# NNP-DWG-125-001-000_PG4_Schematic_Drawin.net
KiCad netlist of a schematic drawn in Altium Designer
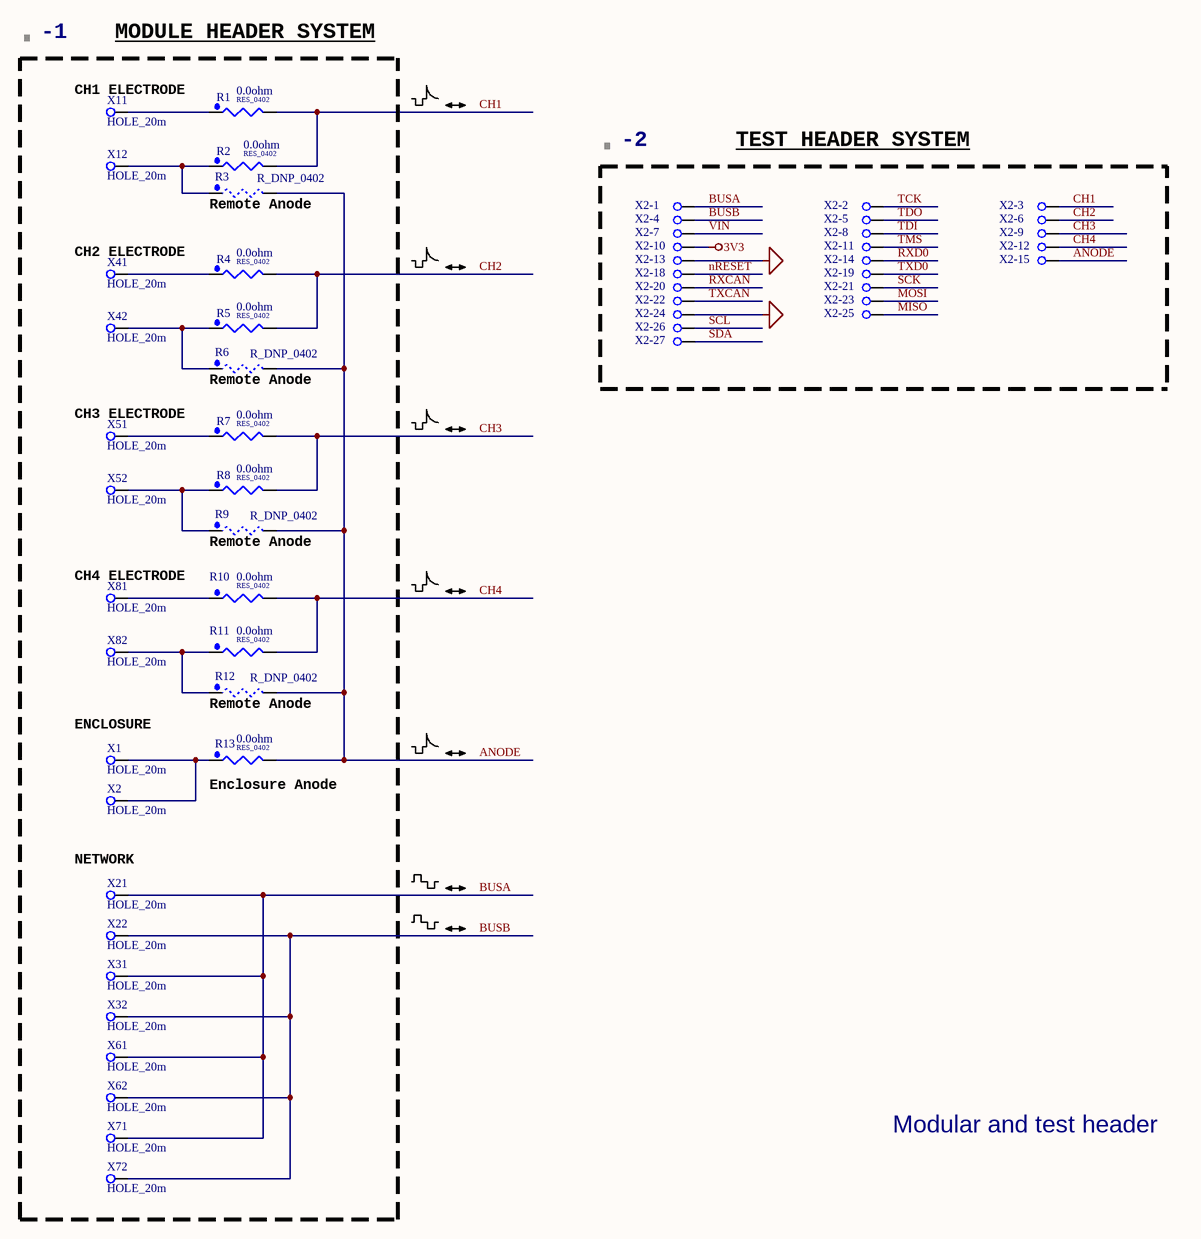
[diagram p0: NNP-DWG-125-001-000 PG4 Schematic Drawing Pg4.SchDoc]

(export (version "E")
  (design (tool "Eeschema 10.0.6"))
  (components
    (comp (ref "-1")
      (value "BOM_S1")
      (description "BOM item small graphic")
      (fields (field (name "XDESCRIPTION") "MODULE HEADER SYSTEM"))
      (libsource (lib "BOM_sym") (part "BOM_S1"))
    )
    (comp (ref "-2")
      (value "BOM_S1")
      (description "BOM item small graphic")
      (fields (field (name "XDESCRIPTION") "TEST HEADER SYSTEM"))
      (libsource (lib "BOM_sym") (part "BOM_S1"))
    )
    (comp (ref "R1")
      (value "0.0ohm")
      (footprint "RES_0402")
      (description "0.0 ohm, 1/16W, 0402, RoHS")
      (fields
        (field (name "MFR") "Vishay Dale")
        (field (name "PACKAGEDESCRIPTION") "RES_0402")
        (field (name "MPN") "CRCW04020000Z0ED")
      )
      (libsource (lib "NNPS Integrated Parts") (part "MCR01MZPJ000"))
    )
    (comp (ref "R2")
      (value "0.0ohm")
      (footprint "RES_0402")
      (description "0.0 ohm, 1/16W, 0402, RoHS")
      (fields
        (field (name "MFR") "Vishay Dale")
        (field (name "PACKAGEDESCRIPTION") "RES_0402")
        (field (name "MPN") "CRCW04020000Z0ED")
      )
      (libsource (lib "NNPS Integrated Parts") (part "MCR01MZPJ000"))
    )
    (comp (ref "R3")
      (value "R_DNP_0402")
      (footprint "RES_0402")
      (description "0.0 ohm 1/16W smd 0402 RoHS")
      (fields (field (name "MFR") "DO NOT POPULATE"))
      (libsource (lib "NNPS Integrated Parts") (part "R_DNP_0402"))
    )
    (comp (ref "R4")
      (value "0.0ohm")
      (footprint "RES_0402")
      (description "0.0 ohm, 1/16W, 0402, RoHS")
      (fields
        (field (name "MFR") "Vishay Dale")
        (field (name "PACKAGEDESCRIPTION") "RES_0402")
        (field (name "MPN") "CRCW04020000Z0ED")
      )
      (libsource (lib "NNPS Integrated Parts") (part "MCR01MZPJ000"))
    )
    (comp (ref "R5")
      (value "0.0ohm")
      (footprint "RES_0402")
      (description "0.0 ohm, 1/16W, 0402, RoHS")
      (fields
        (field (name "MFR") "Vishay Dale")
        (field (name "PACKAGEDESCRIPTION") "RES_0402")
        (field (name "MPN") "CRCW04020000Z0ED")
      )
      (libsource (lib "NNPS Integrated Parts") (part "MCR01MZPJ000"))
    )
    (comp (ref "R6")
      (value "R_DNP_0402")
      (footprint "RES_0402")
      (description "0.0 ohm 1/16W smd 0402 RoHS")
      (fields (field (name "MFR") "DO NOT POPULATE"))
      (libsource (lib "NNPS Integrated Parts") (part "R_DNP_0402"))
    )
    (comp (ref "R7")
      (value "0.0ohm")
      (footprint "RES_0402")
      (description "0.0 ohm, 1/16W, 0402, RoHS")
      (fields
        (field (name "MFR") "Vishay Dale")
        (field (name "PACKAGEDESCRIPTION") "RES_0402")
        (field (name "MPN") "CRCW04020000Z0ED")
      )
      (libsource (lib "NNPS Integrated Parts") (part "MCR01MZPJ000"))
    )
    (comp (ref "R8")
      (value "0.0ohm")
      (footprint "RES_0402")
      (description "0.0 ohm, 1/16W, 0402, RoHS")
      (fields
        (field (name "MFR") "Vishay Dale")
        (field (name "PACKAGEDESCRIPTION") "RES_0402")
        (field (name "MPN") "CRCW04020000Z0ED")
      )
      (libsource (lib "NNPS Integrated Parts") (part "MCR01MZPJ000"))
    )
    (comp (ref "R9")
      (value "R_DNP_0402")
      (footprint "RES_0402")
      (description "0.0 ohm 1/16W smd 0402 RoHS")
      (fields (field (name "MFR") "DO NOT POPULATE"))
      (libsource (lib "NNPS Integrated Parts") (part "R_DNP_0402"))
    )
    (comp (ref "R10")
      (value "0.0ohm")
      (footprint "RES_0402")
      (description "0.0 ohm, 1/16W, 0402, RoHS")
      (fields
        (field (name "MFR") "Vishay Dale")
        (field (name "PACKAGEDESCRIPTION") "RES_0402")
        (field (name "MPN") "CRCW04020000Z0ED")
      )
      (libsource (lib "NNPS Integrated Parts") (part "MCR01MZPJ000"))
    )
    (comp (ref "R11")
      (value "0.0ohm")
      (footprint "RES_0402")
      (description "0.0 ohm, 1/16W, 0402, RoHS")
      (fields
        (field (name "MFR") "Vishay Dale")
        (field (name "PACKAGEDESCRIPTION") "RES_0402")
        (field (name "MPN") "CRCW04020000Z0ED")
      )
      (libsource (lib "NNPS Integrated Parts") (part "MCR01MZPJ000"))
    )
    (comp (ref "R12")
      (value "R_DNP_0402")
      (footprint "RES_0402")
      (description "0.0 ohm 1/16W smd 0402 RoHS")
      (fields (field (name "MFR") "DO NOT POPULATE"))
      (libsource (lib "NNPS Integrated Parts") (part "R_DNP_0402"))
    )
    (comp (ref "R13")
      (value "0.0ohm")
      (footprint "RES_0402")
      (description "0.0 ohm, 1/16W, 0402, RoHS")
      (fields
        (field (name "MFR") "Vishay Dale")
        (field (name "PACKAGEDESCRIPTION") "RES_0402")
        (field (name "MPN") "CRCW04020000Z0ED")
      )
      (libsource (lib "NNPS Integrated Parts") (part "MCR01MZPJ000"))
    )
    (comp (ref "X1")
      (value "HOLE_20m")
      (footprint "FEEDHOLE_20mil")
      (description "Hole for 10mil diameter feedthrough")
      (libsource (lib "NNPS Integrated Parts") (part "HOLE_20m"))
    )
    (comp (ref "X2")
      (value "HOLE_20m")
      (footprint "FEEDHOLE_20mil")
      (description "Hole for 10mil diameter feedthrough")
      (libsource (lib "NNPS Integrated Parts") (part "HOLE_20m"))
    )
    (comp (ref "X2-1")
      (value "0.1\" header hole")
      (footprint "HDR_HOLE_RING")
      (libsource (lib "NNPS Integrated Parts") (part "Header 1x1"))
    )
    (comp (ref "X2-2")
      (value "0.1\" header hole")
      (footprint "HDR_HOLE_RING")
      (libsource (lib "NNPS Integrated Parts") (part "Header 1x1"))
    )
    (comp (ref "X2-3")
      (value "0.1\" header hole")
      (footprint "HDR_HOLE_RING")
      (libsource (lib "NNPS Integrated Parts") (part "Header 1x1"))
    )
    (comp (ref "X2-4")
      (value "0.1\" header hole")
      (footprint "HDR_HOLE_RING")
      (libsource (lib "NNPS Integrated Parts") (part "Header 1x1"))
    )
    (comp (ref "X2-5")
      (value "0.1\" header hole")
      (footprint "HDR_HOLE_RING")
      (libsource (lib "NNPS Integrated Parts") (part "Header 1x1"))
    )
    (comp (ref "X2-6")
      (value "0.1\" header hole")
      (footprint "HDR_HOLE_RING")
      (libsource (lib "NNPS Integrated Parts") (part "Header 1x1"))
    )
    (comp (ref "X2-7")
      (value "0.1\" header hole")
      (footprint "HDR_HOLE_RING")
      (libsource (lib "NNPS Integrated Parts") (part "Header 1x1"))
    )
    (comp (ref "X2-8")
      (value "0.1\" header hole")
      (footprint "HDR_HOLE_RING")
      (libsource (lib "NNPS Integrated Parts") (part "Header 1x1"))
    )
    (comp (ref "X2-9")
      (value "0.1\" header hole")
      (footprint "HDR_HOLE_RING")
      (libsource (lib "NNPS Integrated Parts") (part "Header 1x1"))
    )
    (comp (ref "X2-10")
      (value "0.1\" header hole")
      (footprint "HDR_HOLE_RING")
      (libsource (lib "NNPS Integrated Parts") (part "Header 1x1"))
    )
    (comp (ref "X2-11")
      (value "0.1\" header hole")
      (footprint "HDR_HOLE_RING")
      (libsource (lib "NNPS Integrated Parts") (part "Header 1x1"))
    )
    (comp (ref "X2-12")
      (value "0.1\" header hole")
      (footprint "HDR_HOLE_RING")
      (libsource (lib "NNPS Integrated Parts") (part "Header 1x1"))
    )
    (comp (ref "X2-13")
      (value "0.1\" header hole")
      (footprint "HDR_HOLE_RING")
      (libsource (lib "NNPS Integrated Parts") (part "Header 1x1"))
    )
    (comp (ref "X2-14")
      (value "0.1\" header hole")
      (footprint "HDR_HOLE_RING")
      (libsource (lib "NNPS Integrated Parts") (part "Header 1x1"))
    )
    (comp (ref "X2-15")
      (value "0.1\" header hole")
      (footprint "HDR_HOLE_RING")
      (libsource (lib "NNPS Integrated Parts") (part "Header 1x1"))
    )
    (comp (ref "X2-18")
      (value "0.1\" header hole")
      (footprint "HDR_HOLE_RING")
      (libsource (lib "NNPS Integrated Parts") (part "Header 1x1"))
    )
    (comp (ref "X2-19")
      (value "0.1\" header hole")
      (footprint "HDR_HOLE_RING")
      (libsource (lib "NNPS Integrated Parts") (part "Header 1x1"))
    )
    (comp (ref "X2-20")
      (value "0.1\" header hole")
      (footprint "HDR_HOLE_RING")
      (libsource (lib "NNPS Integrated Parts") (part "Header 1x1"))
    )
    (comp (ref "X2-21")
      (value "0.1\" header hole")
      (footprint "HDR_HOLE_RING")
      (libsource (lib "NNPS Integrated Parts") (part "Header 1x1"))
    )
    (comp (ref "X2-22")
      (value "0.1\" header hole")
      (footprint "HDR_HOLE_RING")
      (libsource (lib "NNPS Integrated Parts") (part "Header 1x1"))
    )
    (comp (ref "X2-23")
      (value "0.1\" header hole")
      (footprint "HDR_HOLE_RING")
      (libsource (lib "NNPS Integrated Parts") (part "Header 1x1"))
    )
    (comp (ref "X2-24")
      (value "0.1\" header hole")
      (footprint "HDR_HOLE_RING")
      (libsource (lib "NNPS Integrated Parts") (part "Header 1x1"))
    )
    (comp (ref "X2-25")
      (value "0.1\" header hole")
      (footprint "HDR_HOLE_RING")
      (libsource (lib "NNPS Integrated Parts") (part "Header 1x1"))
    )
    (comp (ref "X2-26")
      (value "0.1\" header hole")
      (footprint "HDR_HOLE_RING")
      (libsource (lib "NNPS Integrated Parts") (part "Header 1x1"))
    )
    (comp (ref "X2-27")
      (value "0.1\" header hole")
      (footprint "HDR_HOLE_RING")
      (libsource (lib "NNPS Integrated Parts") (part "Header 1x1"))
    )
    (comp (ref "X11")
      (value "HOLE_20m")
      (footprint "FEEDHOLE_20mil")
      (description "Hole for 10mil diameter feedthrough")
      (libsource (lib "NNPS Integrated Parts") (part "HOLE_20m"))
    )
    (comp (ref "X12")
      (value "HOLE_20m")
      (footprint "FEEDHOLE_20mil")
      (description "Hole for 10mil diameter feedthrough")
      (libsource (lib "NNPS Integrated Parts") (part "HOLE_20m"))
    )
    (comp (ref "X21")
      (value "HOLE_20m")
      (footprint "FEEDHOLE_20mil")
      (description "Hole for 10mil diameter feedthrough")
      (libsource (lib "NNPS Integrated Parts") (part "HOLE_20m"))
    )
    (comp (ref "X22")
      (value "HOLE_20m")
      (footprint "FEEDHOLE_20mil")
      (description "Hole for 10mil diameter feedthrough")
      (libsource (lib "NNPS Integrated Parts") (part "HOLE_20m"))
    )
    (comp (ref "X31")
      (value "HOLE_20m")
      (footprint "FEEDHOLE_20mil")
      (description "Hole for 10mil diameter feedthrough")
      (libsource (lib "NNPS Integrated Parts") (part "HOLE_20m"))
    )
    (comp (ref "X32")
      (value "HOLE_20m")
      (footprint "FEEDHOLE_20mil")
      (description "Hole for 10mil diameter feedthrough")
      (libsource (lib "NNPS Integrated Parts") (part "HOLE_20m"))
    )
    (comp (ref "X41")
      (value "HOLE_20m")
      (footprint "FEEDHOLE_20mil")
      (description "Hole for 10mil diameter feedthrough")
      (libsource (lib "NNPS Integrated Parts") (part "HOLE_20m"))
    )
    (comp (ref "X42")
      (value "HOLE_20m")
      (footprint "FEEDHOLE_20mil")
      (description "Hole for 10mil diameter feedthrough")
      (libsource (lib "NNPS Integrated Parts") (part "HOLE_20m"))
    )
    (comp (ref "X51")
      (value "HOLE_20m")
      (footprint "FEEDHOLE_20mil")
      (description "Hole for 10mil diameter feedthrough")
      (libsource (lib "NNPS Integrated Parts") (part "HOLE_20m"))
    )
    (comp (ref "X52")
      (value "HOLE_20m")
      (footprint "FEEDHOLE_20mil")
      (description "Hole for 10mil diameter feedthrough")
      (libsource (lib "NNPS Integrated Parts") (part "HOLE_20m"))
    )
    (comp (ref "X61")
      (value "HOLE_20m")
      (footprint "FEEDHOLE_20mil")
      (description "Hole for 10mil diameter feedthrough")
      (libsource (lib "NNPS Integrated Parts") (part "HOLE_20m"))
    )
    (comp (ref "X62")
      (value "HOLE_20m")
      (footprint "FEEDHOLE_20mil")
      (description "Hole for 10mil diameter feedthrough")
      (libsource (lib "NNPS Integrated Parts") (part "HOLE_20m"))
    )
    (comp (ref "X71")
      (value "HOLE_20m")
      (footprint "FEEDHOLE_20mil")
      (description "Hole for 10mil diameter feedthrough")
      (libsource (lib "NNPS Integrated Parts") (part "HOLE_20m"))
    )
    (comp (ref "X72")
      (value "HOLE_20m")
      (footprint "FEEDHOLE_20mil")
      (description "Hole for 10mil diameter feedthrough")
      (libsource (lib "NNPS Integrated Parts") (part "HOLE_20m"))
    )
    (comp (ref "X81")
      (value "HOLE_20m")
      (footprint "FEEDHOLE_20mil")
      (description "Hole for 10mil diameter feedthrough")
      (libsource (lib "NNPS Integrated Parts") (part "HOLE_20m"))
    )
    (comp (ref "X82")
      (value "HOLE_20m")
      (footprint "FEEDHOLE_20mil")
      (description "Hole for 10mil diameter feedthrough")
      (libsource (lib "NNPS Integrated Parts") (part "HOLE_20m"))
    )
  )
  (nets
    (net (code "1") (name "/ANODE") (class "Default")
      (node (ref "R12") (pin "2") (pinfunction "2_2") (pintype "passive"))
      (node (ref "R13") (pin "2") (pinfunction "2_2") (pintype "passive"))
      (node (ref "R3") (pin "2") (pinfunction "2_2") (pintype "passive"))
      (node (ref "R6") (pin "2") (pinfunction "2_2") (pintype "passive"))
      (node (ref "R9") (pin "2") (pinfunction "2_2") (pintype "passive"))
      (node (ref "X2-15") (pin "1") (pinfunction "1_1") (pintype "passive"))
    )
    (net (code "2") (name "/BUSA") (class "Default")
      (node (ref "X2-1") (pin "1") (pinfunction "1_1") (pintype "passive"))
      (node (ref "X21") (pin "1") (pinfunction "1_1") (pintype "passive"))
      (node (ref "X31") (pin "1") (pinfunction "1_1") (pintype "passive"))
      (node (ref "X61") (pin "1") (pinfunction "1_1") (pintype "passive"))
      (node (ref "X71") (pin "1") (pinfunction "1_1") (pintype "passive"))
    )
    (net (code "3") (name "/BUSB") (class "Default")
      (node (ref "X2-4") (pin "1") (pinfunction "1_1") (pintype "passive"))
      (node (ref "X22") (pin "1") (pinfunction "1_1") (pintype "passive"))
      (node (ref "X32") (pin "1") (pinfunction "1_1") (pintype "passive"))
      (node (ref "X62") (pin "1") (pinfunction "1_1") (pintype "passive"))
      (node (ref "X72") (pin "1") (pinfunction "1_1") (pintype "passive"))
    )
    (net (code "4") (name "/CH1") (class "Default")
      (node (ref "R1") (pin "2") (pinfunction "2_2") (pintype "passive"))
      (node (ref "R2") (pin "2") (pinfunction "2_2") (pintype "passive"))
      (node (ref "X2-3") (pin "1") (pinfunction "1_1") (pintype "passive"))
    )
    (net (code "5") (name "/CH2") (class "Default")
      (node (ref "R4") (pin "2") (pinfunction "2_2") (pintype "passive"))
      (node (ref "R5") (pin "2") (pinfunction "2_2") (pintype "passive"))
      (node (ref "X2-6") (pin "1") (pinfunction "1_1") (pintype "passive"))
    )
    (net (code "6") (name "/CH3") (class "Default")
      (node (ref "R7") (pin "2") (pinfunction "2_2") (pintype "passive"))
      (node (ref "R8") (pin "2") (pinfunction "2_2") (pintype "passive"))
      (node (ref "X2-9") (pin "1") (pinfunction "1_1") (pintype "passive"))
    )
    (net (code "7") (name "/CH4") (class "Default")
      (node (ref "R10") (pin "2") (pinfunction "2_2") (pintype "passive"))
      (node (ref "R11") (pin "2") (pinfunction "2_2") (pintype "passive"))
      (node (ref "X2-12") (pin "1") (pinfunction "1_1") (pintype "passive"))
    )
    (net (code "8") (name "/MISO") (class "Default")
      (node (ref "X2-25") (pin "1") (pinfunction "1_1") (pintype "passive"))
    )
    (net (code "9") (name "/MOSI") (class "Default")
      (node (ref "X2-23") (pin "1") (pinfunction "1_1") (pintype "passive"))
    )
    (net (code "10") (name "/RXCAN") (class "Default")
      (node (ref "X2-20") (pin "1") (pinfunction "1_1") (pintype "passive"))
    )
    (net (code "11") (name "/RXD0") (class "Default")
      (node (ref "X2-14") (pin "1") (pinfunction "1_1") (pintype "passive"))
    )
    (net (code "12") (name "/SCK") (class "Default")
      (node (ref "X2-21") (pin "1") (pinfunction "1_1") (pintype "passive"))
    )
    (net (code "13") (name "/SCL") (class "Default")
      (node (ref "X2-26") (pin "1") (pinfunction "1_1") (pintype "passive"))
    )
    (net (code "14") (name "/SDA") (class "Default")
      (node (ref "X2-27") (pin "1") (pinfunction "1_1") (pintype "passive"))
    )
    (net (code "15") (name "/TCK") (class "Default")
      (node (ref "X2-2") (pin "1") (pinfunction "1_1") (pintype "passive"))
    )
    (net (code "16") (name "/TDI") (class "Default")
      (node (ref "X2-8") (pin "1") (pinfunction "1_1") (pintype "passive"))
    )
    (net (code "17") (name "/TDO") (class "Default")
      (node (ref "X2-5") (pin "1") (pinfunction "1_1") (pintype "passive"))
    )
    (net (code "18") (name "/TMS") (class "Default")
      (node (ref "X2-11") (pin "1") (pinfunction "1_1") (pintype "passive"))
    )
    (net (code "19") (name "/TXCAN") (class "Default")
      (node (ref "X2-22") (pin "1") (pinfunction "1_1") (pintype "passive"))
    )
    (net (code "20") (name "/TXD0") (class "Default")
      (node (ref "X2-19") (pin "1") (pinfunction "1_1") (pintype "passive"))
    )
    (net (code "21") (name "/VIN") (class "Default")
      (node (ref "X2-7") (pin "1") (pinfunction "1_1") (pintype "passive"))
    )
    (net (code "22") (name "/nRESET") (class "Default")
      (node (ref "X2-18") (pin "1") (pinfunction "1_1") (pintype "passive"))
    )
    (net (code "23") (name "3V3") (class "Default")
      (node (ref "X2-10") (pin "1") (pinfunction "1_1") (pintype "passive"))
    )
    (net (code "24") (name "GND") (class "Default")
      (node (ref "X2-13") (pin "1") (pinfunction "1_1") (pintype "passive"))
      (node (ref "X2-24") (pin "1") (pinfunction "1_1") (pintype "passive"))
    )
    (net (code "25") (name "Net-(R1-Pad1)") (class "Default")
      (node (ref "R1") (pin "1") (pinfunction "1_1") (pintype "passive"))
      (node (ref "X11") (pin "1") (pinfunction "1_1") (pintype "passive"))
    )
    (net (code "26") (name "Net-(R2-Pad1)") (class "Default")
      (node (ref "R2") (pin "1") (pinfunction "1_1") (pintype "passive"))
      (node (ref "R3") (pin "1") (pinfunction "1_1") (pintype "passive"))
      (node (ref "X12") (pin "1") (pinfunction "1_1") (pintype "passive"))
    )
    (net (code "27") (name "Net-(R4-Pad1)") (class "Default")
      (node (ref "R4") (pin "1") (pinfunction "1_1") (pintype "passive"))
      (node (ref "X41") (pin "1") (pinfunction "1_1") (pintype "passive"))
    )
    (net (code "28") (name "Net-(R5-Pad1)") (class "Default")
      (node (ref "R5") (pin "1") (pinfunction "1_1") (pintype "passive"))
      (node (ref "R6") (pin "1") (pinfunction "1_1") (pintype "passive"))
      (node (ref "X42") (pin "1") (pinfunction "1_1") (pintype "passive"))
    )
    (net (code "29") (name "Net-(R7-Pad1)") (class "Default")
      (node (ref "R7") (pin "1") (pinfunction "1_1") (pintype "passive"))
      (node (ref "X51") (pin "1") (pinfunction "1_1") (pintype "passive"))
    )
    (net (code "30") (name "Net-(R8-Pad1)") (class "Default")
      (node (ref "R8") (pin "1") (pinfunction "1_1") (pintype "passive"))
      (node (ref "R9") (pin "1") (pinfunction "1_1") (pintype "passive"))
      (node (ref "X52") (pin "1") (pinfunction "1_1") (pintype "passive"))
    )
    (net (code "31") (name "Net-(R10-Pad1)") (class "Default")
      (node (ref "R10") (pin "1") (pinfunction "1_1") (pintype "passive"))
      (node (ref "X81") (pin "1") (pinfunction "1_1") (pintype "passive"))
    )
    (net (code "32") (name "Net-(R11-Pad1)") (class "Default")
      (node (ref "R11") (pin "1") (pinfunction "1_1") (pintype "passive"))
      (node (ref "R12") (pin "1") (pinfunction "1_1") (pintype "passive"))
      (node (ref "X82") (pin "1") (pinfunction "1_1") (pintype "passive"))
    )
    (net (code "33") (name "Net-(R13-Pad1)") (class "Default")
      (node (ref "R13") (pin "1") (pinfunction "1_1") (pintype "passive"))
      (node (ref "X1") (pin "1") (pinfunction "1_1") (pintype "passive"))
      (node (ref "X2") (pin "1") (pinfunction "1_1") (pintype "passive"))
    )
  )
)
